# pcb_New.net
KiCad netlist of a schematic drawn in EAGLE
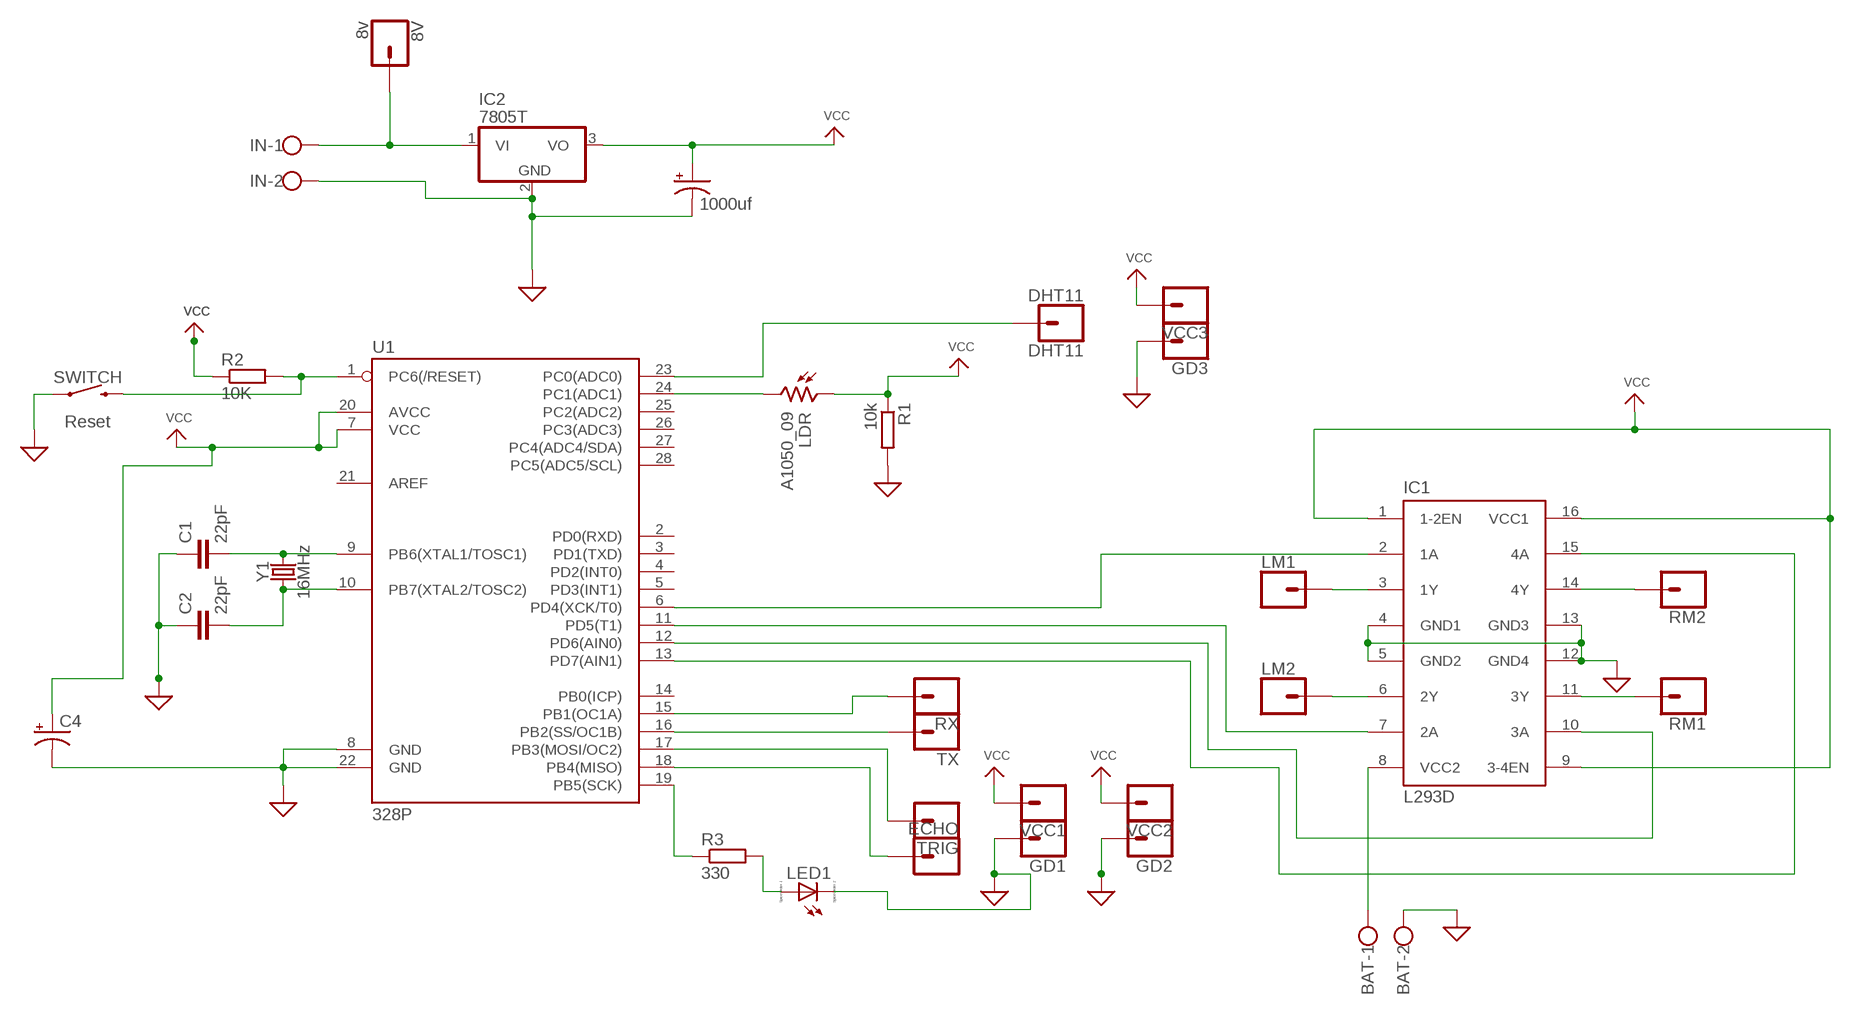
[diagram p0: schematic, sheet 1]

(export (version "E")
  (design (tool "Eeschema 10.0.6"))
  (components
    (comp (ref "8V")
      (value "8v")
      (footprint "eagle-import:1X01")
      (libsource (lib "eagle-import") (part "CONN_01"))
    )
    (comp (ref "BAT")
      (value "W237-102")
      (footprint "eagle-import:W237-102")
      (fields (field (name "MPN") "237-102"))
      (libsource (lib "eagle-import") (part "W237-102"))
    )
    (comp (ref "C1")
      (value "22pF")
      (footprint "eagle-import:CAP-PTH-2.54")
      (libsource (lib "eagle-import") (part "22PF-PTH-2.54MM-200V-5%"))
    )
    (comp (ref "C2")
      (value "22pF")
      (footprint "eagle-import:CAP-PTH-2.54")
      (libsource (lib "eagle-import") (part "22PF-PTH-2.54MM-200V-5%"))
    )
    (comp (ref "C3")
      (value "1000uf")
      (footprint "eagle-import:E3,5-8")
      (libsource (lib "eagle-import") (part "CAPACITOR-PE3.5-8"))
    )
    (comp (ref "C4")
      (value "CAPACITOR-PE3.5-8")
      (footprint "eagle-import:E3,5-8")
      (libsource (lib "eagle-import") (part "CAPACITOR-PE3.5-8"))
    )
    (comp (ref "DHT11")
      (value "DHT11")
      (footprint "eagle-import:1X01")
      (libsource (lib "eagle-import") (part "CONN_01"))
    )
    (comp (ref "ECHO")
      (value "CONN_01")
      (footprint "eagle-import:1X01")
      (libsource (lib "eagle-import") (part "CONN_01"))
    )
    (comp (ref "GD1")
      (value "CONN_01")
      (footprint "eagle-import:1X01")
      (libsource (lib "eagle-import") (part "CONN_01"))
    )
    (comp (ref "GD2")
      (value "CONN_01")
      (footprint "eagle-import:1X01")
      (libsource (lib "eagle-import") (part "CONN_01"))
    )
    (comp (ref "GD3")
      (value "CONN_01")
      (footprint "eagle-import:1X01")
      (libsource (lib "eagle-import") (part "CONN_01"))
    )
    (comp (ref "IC1")
      (value "L293D")
      (footprint "eagle-import:DIL16")
      (libsource (lib "eagle-import") (part "L293D"))
    )
    (comp (ref "IC2")
      (value "7805T")
      (footprint "eagle-import:TO220H")
      (libsource (lib "eagle-import") (part "78T05"))
    )
    (comp (ref "IN")
      (value "W237-102")
      (footprint "eagle-import:W237-102")
      (fields (field (name "MPN") "237-102"))
      (libsource (lib "eagle-import") (part "W237-102"))
    )
    (comp (ref "LDR")
      (value "A1050_09")
      (footprint "eagle-import:T0-46-A10XX")
      (libsource (lib "eagle-import") (part "A1050_09"))
    )
    (comp (ref "LED1")
      (value "LED_ELD260")
      (footprint "eagle-import:LED_LD260")
      (libsource (lib "eagle-import") (part "LED_ELD260"))
    )
    (comp (ref "LM1")
      (value "CONN_01")
      (footprint "eagle-import:1X01")
      (libsource (lib "eagle-import") (part "CONN_01"))
    )
    (comp (ref "LM2")
      (value "CONN_01")
      (footprint "eagle-import:1X01")
      (libsource (lib "eagle-import") (part "CONN_01"))
    )
    (comp (ref "R1")
      (value "10k")
      (footprint "eagle-import:0204_7")
      (libsource (lib "eagle-import") (part "R-EU_0204/7"))
    )
    (comp (ref "R2")
      (value "10K")
      (footprint "eagle-import:0204_7")
      (libsource (lib "eagle-import") (part "R-EU_0204/7"))
    )
    (comp (ref "R3")
      (value "330")
      (footprint "eagle-import:0204_7")
      (libsource (lib "eagle-import") (part "R-EU_0204/7"))
    )
    (comp (ref "RM1")
      (value "CONN_01")
      (footprint "eagle-import:1X01")
      (libsource (lib "eagle-import") (part "CONN_01"))
    )
    (comp (ref "RM2")
      (value "CONN_01")
      (footprint "eagle-import:1X01")
      (libsource (lib "eagle-import") (part "CONN_01"))
    )
    (comp (ref "RX")
      (value "CONN_01")
      (footprint "eagle-import:1X01")
      (libsource (lib "eagle-import") (part "CONN_01"))
    )
    (comp (ref "SWITCH")
      (value "Reset")
      (footprint "eagle-import:TACTILE_SWITCH_PTH_6.0MM")
      (libsource (lib "eagle-import") (part "MOMENTARY-SWITCH-SPST-PTH-6.0MM"))
    )
    (comp (ref "TRIG")
      (value "CONN_01")
      (footprint "eagle-import:1X01")
      (libsource (lib "eagle-import") (part "CONN_01"))
    )
    (comp (ref "TX")
      (value "CONN_01")
      (footprint "eagle-import:1X01")
      (libsource (lib "eagle-import") (part "CONN_01"))
    )
    (comp (ref "U1")
      (value "328P")
      (footprint "eagle-import:DIP28")
      (libsource (lib "eagle-import") (part "ATMEGA328P_PDIP"))
    )
    (comp (ref "VCC1")
      (value "CONN_01")
      (footprint "eagle-import:1X01")
      (libsource (lib "eagle-import") (part "CONN_01"))
    )
    (comp (ref "VCC2")
      (value "CONN_01")
      (footprint "eagle-import:1X01")
      (libsource (lib "eagle-import") (part "CONN_01"))
    )
    (comp (ref "VCC3")
      (value "CONN_01")
      (footprint "eagle-import:1X01")
      (libsource (lib "eagle-import") (part "CONN_01"))
    )
    (comp (ref "Y1")
      (value "16MHz")
      (footprint "eagle-import:HC49US")
      (libsource (lib "eagle-import") (part "CRYSTAL-16MHZPTH-HC49US"))
    )
  )
  (nets
    (net (code "1") (name "Net-(BATA-KL)") (class "Default")
      (node (ref "BAT") (pin "1") (pinfunction "KL_1") (pintype "passive"))
      (node (ref "IC1") (pin "8") (pinfunction "VCC2_8") (pintype "power_in"))
    )
    (net (code "2") (name "Net-(IC1-1A)") (class "Default")
      (node (ref "IC1") (pin "2") (pinfunction "1A_2") (pintype "input"))
      (node (ref "U1") (pin "6") (pinfunction "PD4(XCK/T0)_6") (pintype "bidirectional"))
    )
    (net (code "3") (name "Net-(IC1-1Y)") (class "Default")
      (node (ref "IC1") (pin "3") (pinfunction "1Y_3") (pintype "output"))
      (node (ref "LM1") (pin "1") (pinfunction "1_1") (pintype "passive"))
    )
    (net (code "4") (name "Net-(IC1-2A)") (class "Default")
      (node (ref "IC1") (pin "7") (pinfunction "2A_7") (pintype "input"))
      (node (ref "U1") (pin "11") (pinfunction "PD5(T1)_11") (pintype "bidirectional"))
    )
    (net (code "5") (name "Net-(IC1-2Y)") (class "Default")
      (node (ref "IC1") (pin "6") (pinfunction "2Y_6") (pintype "output"))
      (node (ref "LM2") (pin "1") (pinfunction "1_1") (pintype "passive"))
    )
    (net (code "6") (name "Net-(IC1-3A)") (class "Default")
      (node (ref "IC1") (pin "10") (pinfunction "3A_10") (pintype "input"))
      (node (ref "U1") (pin "12") (pinfunction "PD6(AIN0)_12") (pintype "bidirectional"))
    )
    (net (code "7") (name "Net-(IC1-3Y)") (class "Default")
      (node (ref "IC1") (pin "11") (pinfunction "3Y_11") (pintype "output"))
      (node (ref "RM1") (pin "1") (pinfunction "1_1") (pintype "passive"))
    )
    (net (code "8") (name "Net-(IC1-4A)") (class "Default")
      (node (ref "IC1") (pin "15") (pinfunction "4A_15") (pintype "input"))
      (node (ref "U1") (pin "13") (pinfunction "PD7(AIN1)_13") (pintype "bidirectional"))
    )
    (net (code "9") (name "Net-(IC1-4Y)") (class "Default")
      (node (ref "IC1") (pin "14") (pinfunction "4Y_14") (pintype "output"))
      (node (ref "RM2") (pin "1") (pinfunction "1_1") (pintype "passive"))
    )
    (net (code "10") (name "Net-(IC2-VI)") (class "Default")
      (node (ref "8V") (pin "1") (pinfunction "1_1") (pintype "passive"))
      (node (ref "IC2") (pin "1") (pinfunction "VI_1") (pintype "input"))
      (node (ref "IN") (pin "1") (pinfunction "KL_1") (pintype "passive"))
    )
    (net (code "11") (name "Net-(LED1-PadA)") (class "Default")
      (node (ref "LED1") (pin "A") (pinfunction "A_A") (pintype "passive"))
      (node (ref "R3") (pin "2") (pinfunction "2_2") (pintype "passive"))
    )
    (net (code "12") (name "Net-(SWITCH-2)") (class "Default")
      (node (ref "R2") (pin "2") (pinfunction "2_2") (pintype "passive"))
      (node (ref "SWITCH") (pin "3") (pinfunction "2_3") (pintype "passive"))
      (node (ref "U1") (pin "1") (pinfunction "PC6(/RESET)_1") (pintype "bidirectional"))
    )
    (net (code "13") (name "Net-(U1-PB1(OC1A))") (class "Default")
      (node (ref "RX") (pin "1") (pinfunction "1_1") (pintype "passive"))
      (node (ref "U1") (pin "15") (pinfunction "PB1(OC1A)_15") (pintype "bidirectional"))
    )
    (net (code "14") (name "Net-(U1-PB2(SS{slash}OC1B))") (class "Default")
      (node (ref "TX") (pin "1") (pinfunction "1_1") (pintype "passive"))
      (node (ref "U1") (pin "16") (pinfunction "PB2(SS/OC1B)_16") (pintype "bidirectional"))
    )
    (net (code "15") (name "Net-(U1-PB3(MOSI{slash}OC2))") (class "Default")
      (node (ref "TRIG") (pin "1") (pinfunction "1_1") (pintype "passive"))
      (node (ref "U1") (pin "17") (pinfunction "PB3(MOSI/OC2)_17") (pintype "bidirectional"))
    )
    (net (code "16") (name "Net-(U1-PB4(MISO))") (class "Default")
      (node (ref "ECHO") (pin "1") (pinfunction "1_1") (pintype "passive"))
      (node (ref "U1") (pin "18") (pinfunction "PB4(MISO)_18") (pintype "bidirectional"))
    )
    (net (code "17") (name "Net-(U1-PB5(SCK))") (class "Default")
      (node (ref "R3") (pin "1") (pinfunction "1_1") (pintype "passive"))
      (node (ref "U1") (pin "19") (pinfunction "PB5(SCK)_19") (pintype "bidirectional"))
    )
    (net (code "18") (name "Net-(U1-PB6(XTAL1{slash}TOSC1))") (class "Default")
      (node (ref "C1") (pin "2") (pinfunction "2_2") (pintype "passive"))
      (node (ref "U1") (pin "9") (pinfunction "PB6(XTAL1/TOSC1)_9") (pintype "bidirectional"))
      (node (ref "Y1") (pin "2") (pinfunction "2_2") (pintype "passive"))
    )
    (net (code "19") (name "Net-(U1-PB7(XTAL2{slash}TOSC2))") (class "Default")
      (node (ref "C2") (pin "2") (pinfunction "2_2") (pintype "passive"))
      (node (ref "U1") (pin "10") (pinfunction "PB7(XTAL2/TOSC2)_10") (pintype "bidirectional"))
      (node (ref "Y1") (pin "1") (pinfunction "1_1") (pintype "passive"))
    )
    (net (code "20") (name "Net-(U1-PC0(ADC0))") (class "Default")
      (node (ref "DHT11") (pin "1") (pinfunction "1_1") (pintype "passive"))
      (node (ref "U1") (pin "23") (pinfunction "PC0(ADC0)_23") (pintype "bidirectional"))
    )
    (net (code "21") (name "Net-(U1-PC1(ADC1))") (class "Default")
      (node (ref "LDR") (pin "2") (pinfunction "2_2") (pintype "passive"))
      (node (ref "U1") (pin "24") (pinfunction "PC1(ADC1)_24") (pintype "bidirectional"))
    )
    (net (code "22") (name "SUP") (class "Default")
      (node (ref "BAT") (pin "2") (pinfunction "KL_2") (pintype "passive"))
      (node (ref "C1") (pin "1") (pinfunction "1_1") (pintype "passive"))
      (node (ref "C2") (pin "1") (pinfunction "1_1") (pintype "passive"))
      (node (ref "C3") (pin "-") (pinfunction "-_-") (pintype "passive"))
      (node (ref "C4") (pin "-") (pinfunction "-_-") (pintype "passive"))
      (node (ref "GD1") (pin "1") (pinfunction "1_1") (pintype "passive"))
      (node (ref "GD2") (pin "1") (pinfunction "1_1") (pintype "passive"))
      (node (ref "GD3") (pin "1") (pinfunction "1_1") (pintype "passive"))
      (node (ref "IC1") (pin "12") (pinfunction "GND4_12") (pintype "power_in"))
      (node (ref "IC1") (pin "13") (pinfunction "GND3_13") (pintype "power_in"))
      (node (ref "IC1") (pin "4") (pinfunction "GND1_4") (pintype "power_in"))
      (node (ref "IC1") (pin "5") (pinfunction "GND2_5") (pintype "power_in"))
      (node (ref "IC2") (pin "2") (pinfunction "GND_2") (pintype "passive"))
      (node (ref "IN") (pin "2") (pinfunction "KL_2") (pintype "passive"))
      (node (ref "LED1") (pin "K") (pinfunction "C_K") (pintype "passive"))
      (node (ref "R1") (pin "2") (pinfunction "2_2") (pintype "passive"))
      (node (ref "SWITCH") (pin "1") (pinfunction "1_1") (pintype "passive"))
      (node (ref "U1") (pin "22") (pinfunction "GND_22") (pintype "bidirectional"))
      (node (ref "U1") (pin "8") (pinfunction "GND_8") (pintype "bidirectional"))
    )
    (net (code "23") (name "VCC") (class "Default")
      (node (ref "C3") (pin "+") (pinfunction "+_+") (pintype "passive"))
      (node (ref "C4") (pin "+") (pinfunction "+_+") (pintype "passive"))
      (node (ref "IC1") (pin "1") (pinfunction "1-2EN_1") (pintype "input"))
      (node (ref "IC1") (pin "16") (pinfunction "VCC1_16") (pintype "power_in"))
      (node (ref "IC1") (pin "9") (pinfunction "3-4EN_9") (pintype "input"))
      (node (ref "IC2") (pin "3") (pinfunction "VO_3") (pintype "passive"))
      (node (ref "LDR") (pin "1") (pinfunction "1_1") (pintype "passive"))
      (node (ref "R1") (pin "1") (pinfunction "1_1") (pintype "passive"))
      (node (ref "R2") (pin "1") (pinfunction "1_1") (pintype "passive"))
      (node (ref "U1") (pin "20") (pinfunction "AVCC_20") (pintype "bidirectional"))
      (node (ref "U1") (pin "7") (pinfunction "VCC_7") (pintype "bidirectional"))
      (node (ref "VCC1") (pin "1") (pinfunction "1_1") (pintype "passive"))
      (node (ref "VCC2") (pin "1") (pinfunction "1_1") (pintype "passive"))
      (node (ref "VCC3") (pin "1") (pinfunction "1_1") (pintype "passive"))
    )
    (net (code "24") (name "unconnected-(U1-AREF-Pad21)") (class "Default")
      (node (ref "U1") (pin "21") (pinfunction "AREF_21") (pintype "bidirectional"))
    )
    (net (code "25") (name "unconnected-(U1-PB0(ICP)-Pad14)") (class "Default")
      (node (ref "U1") (pin "14") (pinfunction "PB0(ICP)_14") (pintype "bidirectional"))
    )
    (net (code "26") (name "unconnected-(U1-PC2(ADC2)-Pad25)") (class "Default")
      (node (ref "U1") (pin "25") (pinfunction "PC2(ADC2)_25") (pintype "bidirectional"))
    )
    (net (code "27") (name "unconnected-(U1-PC3(ADC3)-Pad26)") (class "Default")
      (node (ref "U1") (pin "26") (pinfunction "PC3(ADC3)_26") (pintype "bidirectional"))
    )
    (net (code "28") (name "unconnected-(U1-PC4(ADC4{slash}SDA)-Pad27)") (class "Default")
      (node (ref "U1") (pin "27") (pinfunction "PC4(ADC4/SDA)_27") (pintype "bidirectional"))
    )
    (net (code "29") (name "unconnected-(U1-PC5(ADC5{slash}SCL)-Pad28)") (class "Default")
      (node (ref "U1") (pin "28") (pinfunction "PC5(ADC5/SCL)_28") (pintype "bidirectional"))
    )
    (net (code "30") (name "unconnected-(U1-PD0(RXD)-Pad2)") (class "Default")
      (node (ref "U1") (pin "2") (pinfunction "PD0(RXD)_2") (pintype "bidirectional"))
    )
    (net (code "31") (name "unconnected-(U1-PD1(TXD)-Pad3)") (class "Default")
      (node (ref "U1") (pin "3") (pinfunction "PD1(TXD)_3") (pintype "bidirectional"))
    )
    (net (code "32") (name "unconnected-(U1-PD2(INT0)-Pad4)") (class "Default")
      (node (ref "U1") (pin "4") (pinfunction "PD2(INT0)_4") (pintype "bidirectional"))
    )
    (net (code "33") (name "unconnected-(U1-PD3(INT1)-Pad5)") (class "Default")
      (node (ref "U1") (pin "5") (pinfunction "PD3(INT1)_5") (pintype "bidirectional"))
    )
  )
)
